# Schematic.net
KiCad netlist of a schematic drawn in Altium Designer
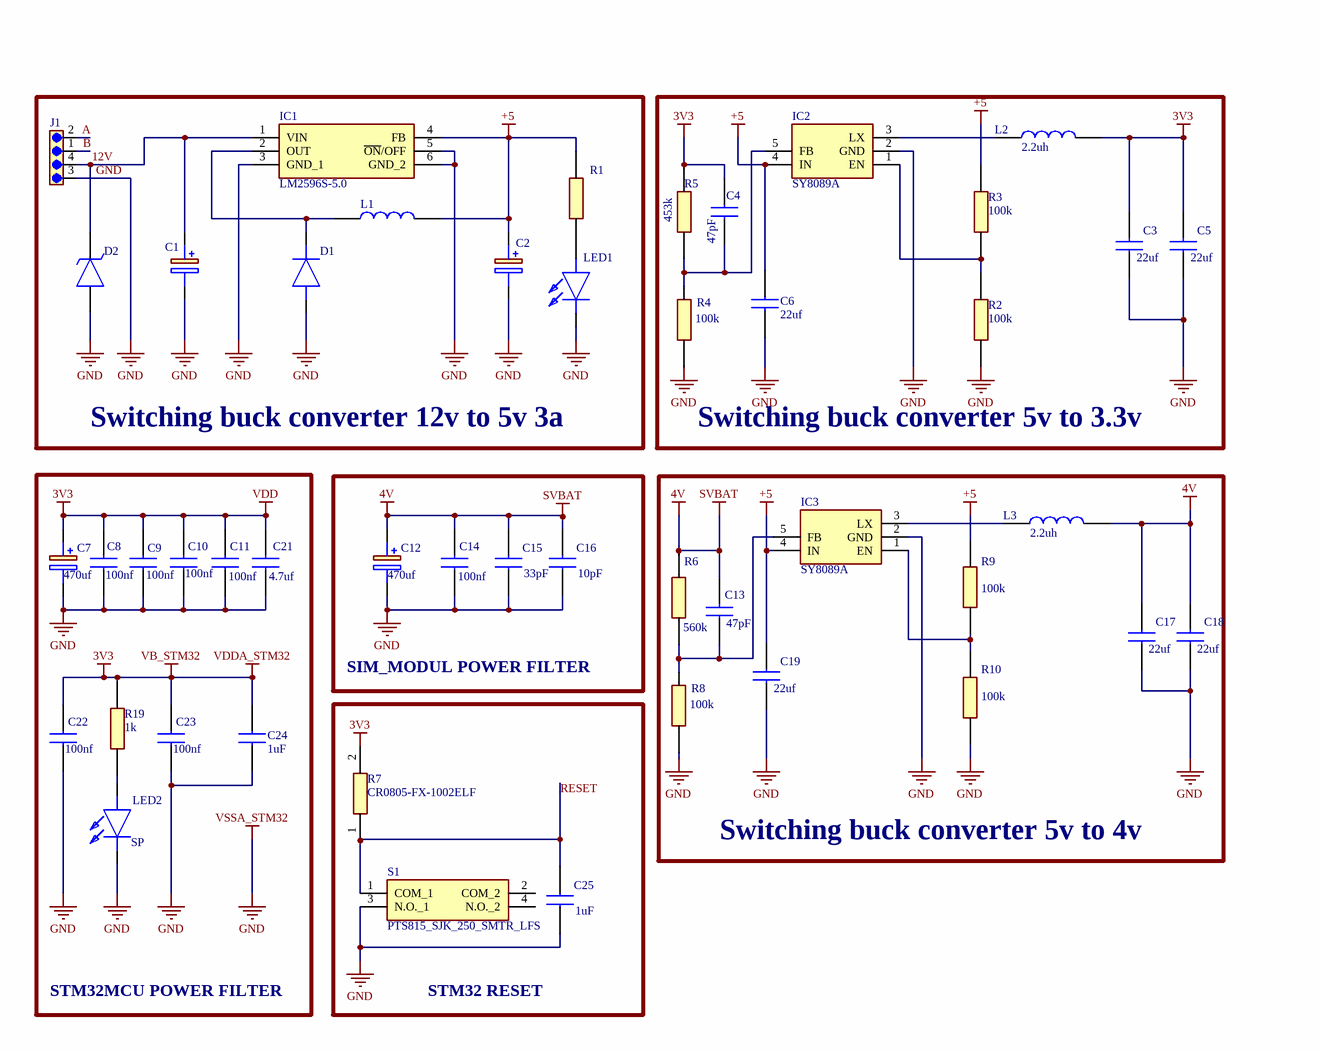
[diagram p0: Schematic.SchDoc, left]

(export (version "E")
  (design (tool "Eeschema 10.0.6"))
  (components
    (comp (ref "C1")
      (value "B40900B5477M000")
      (footprint "BGA129C50P13X13_700X700X60:CAPAE1030X1280N")
      (description "Capacitor Polarised")
      (fields (field (name "MOUSER PART NUMBER") "871-B40900B5477M000"))
      (libsource (lib "*") (part "B40900B5477M000"))
    )
    (comp (ref "C2")
      (value "220uf")
      (footprint "BGA129C50P13X13_700X700X60:CAPPM7344X310N")
      (description "Capacitor Polarised 220uf 10v smd tantalum Part Number: TAJD227K010RNJ")
      (fields
        (field (name "MANUFACTURER_PART_NUMBER") "TAJD227K010RNJ")
        (field (name "MOUSER PART NUMBER") "581-TAJD227K010R")
      )
      (libsource (lib "*") (part "TAJD227K010RNJ"))
    )
    (comp (ref "C3")
      (value "22uf")
      (footprint "BGA129C50P13X13_700X700X60:CAPC2012X140N")
      (description "Capacitor")
      (fields (field (name "MANUFACTURER_PART_NUMBER") "CL21X226MQQNNNE"))
      (libsource (lib "*") (part "CL21X226MQQNNNE"))
    )
    (comp (ref "C4")
      (value "47pF")
      (footprint "BGA129C50P13X13_700X700X60:C0603")
      (description "Capacitor Part Number: C0603H470J5GACTU 47pf 50v 0603")
      (fields
        (field (name "MANUFACTURER_PART_NUMBER") "C0603H470J5GACTU")
        (field (name "MOUSER PART NUMBER") "80-C0603H470J5GACTU")
      )
      (libsource (lib "STM32WB55VGQ6") (part "C0603H470J5GACTU"))
    )
    (comp (ref "C5")
      (value "22uf")
      (footprint "BGA129C50P13X13_700X700X60:CAPC2012X140N")
      (description "Capacitor")
      (fields (field (name "MANUFACTURER_PART_NUMBER") "CL21X226MQQNNNE"))
      (libsource (lib "*") (part "CL21X226MQQNNNE"))
    )
    (comp (ref "C6")
      (value "22uf")
      (footprint "BGA129C50P13X13_700X700X60:CAPC2012X140N")
      (description "Capacitor")
      (fields (field (name "MANUFACTURER_PART_NUMBER") "CL21X226MQQNNNE"))
      (libsource (lib "*") (part "CL21X226MQQNNNE"))
    )
    (comp (ref "C7")
      (value "470uf")
      (footprint "BGA129C50P13X13_700X700X60:T495D")
      (description "Capacitor Polarised")
      (fields
        (field (name "MANUFACTURER_PART_NUMBER") "T495D477K006ATE100")
        (field (name "MOUSER PART NUMBER") "80-T495D477K006E100")
      )
      (libsource (lib "STM32WB55VGQ6") (part "T495D477K006ATE100"))
    )
    (comp (ref "C8")
      (value "100nf")
      (footprint "BGA129C50P13X13_700X700X60:CAPC1608X90N")
      (description "Capacitor")
      (fields
        (field (name "MANUFACTURER_PART_NUMBER") "06036C104MAZ2A")
        (field (name "MOUSER PART NUMBER") "581-06036C104MAZ2A")
      )
      (libsource (lib "*") (part "06036C104MAZ2A"))
    )
    (comp (ref "C9")
      (value "100nf")
      (footprint "BGA129C50P13X13_700X700X60:CAPC1608X90N")
      (description "Capacitor")
      (fields
        (field (name "MANUFACTURER_PART_NUMBER") "06036C104MAZ2A")
        (field (name "MOUSER PART NUMBER") "581-06036C104MAZ2A")
      )
      (libsource (lib "*") (part "06036C104MAZ2A"))
    )
    (comp (ref "C10")
      (value "100nf")
      (footprint "BGA129C50P13X13_700X700X60:CAPC1608X90N")
      (description "Capacitor")
      (fields
        (field (name "MANUFACTURER_PART_NUMBER") "06036C104MAZ2A")
        (field (name "MOUSER PART NUMBER") "581-06036C104MAZ2A")
      )
      (libsource (lib "*") (part "06036C104MAZ2A"))
    )
    (comp (ref "C11")
      (value "100nf")
      (footprint "BGA129C50P13X13_700X700X60:CAPC1608X90N")
      (description "Capacitor")
      (fields
        (field (name "MANUFACTURER_PART_NUMBER") "06036C104MAZ2A")
        (field (name "MOUSER PART NUMBER") "581-06036C104MAZ2A")
      )
      (libsource (lib "*") (part "06036C104MAZ2A"))
    )
    (comp (ref "C12")
      (value "470uf")
      (footprint "BGA129C50P13X13_700X700X60:T495D")
      (description "Capacitor Polarised")
      (fields
        (field (name "MANUFACTURER_PART_NUMBER") "T495D477K006ATE100")
        (field (name "MOUSER PART NUMBER") "80-T495D477K006E100")
      )
      (libsource (lib "STM32WB55VGQ6") (part "T495D477K006ATE100"))
    )
    (comp (ref "C13")
      (value "47pF")
      (footprint "BGA129C50P13X13_700X700X60:C0603")
      (description "Capacitor Part Number: C0603H470J5GACTU 47pf 50v 0603")
      (fields
        (field (name "MANUFACTURER_PART_NUMBER") "C0603H470J5GACTU")
        (field (name "MOUSER PART NUMBER") "80-C0603H470J5GACTU")
      )
      (libsource (lib "STM32WB55VGQ6") (part "C0603H470J5GACTU"))
    )
    (comp (ref "C14")
      (value "100nf")
      (footprint "BGA129C50P13X13_700X700X60:CAPC1608X90N")
      (description "Capacitor")
      (fields
        (field (name "MANUFACTURER_PART_NUMBER") "06036C104MAZ2A")
        (field (name "MOUSER PART NUMBER") "581-06036C104MAZ2A")
      )
      (libsource (lib "*") (part "06036C104MAZ2A"))
    )
    (comp (ref "C15")
      (value "33pF")
      (footprint "BGA129C50P13X13_700X700X60:CAPC0603X33N")
      (description "Capacitor")
      (fields
        (field (name "MANUFACTURER_PART_NUMBER") "GJM0335C0J330JB01D")
        (field (name "MOUSER PART NUMBER") "81-GJM0335C0J330JB1D")
      )
      (libsource (lib "*") (part "GJM0335C0J330JB01D"))
    )
    (comp (ref "C16")
      (value "10pF")
      (footprint "BGA129C50P13X13_700X700X60:CAPC1608X90N")
      (description "Capacitor")
      (fields
        (field (name "MANUFACTURER_PART_NUMBER") "CC0603JRNPO9BN100")
        (field (name "MOUSER PART NUMBER") "603-C0603JRNPO9BN100")
      )
      (libsource (lib "*") (part "CC0603JRNPO9BN100"))
    )
    (comp (ref "C17")
      (value "22uf")
      (footprint "BGA129C50P13X13_700X700X60:CAPC2012X140N")
      (description "Capacitor")
      (fields (field (name "MANUFACTURER_PART_NUMBER") "CL21X226MQQNNNE"))
      (libsource (lib "*") (part "CL21X226MQQNNNE"))
    )
    (comp (ref "C18")
      (value "22uf")
      (footprint "BGA129C50P13X13_700X700X60:CAPC2012X140N")
      (description "Capacitor")
      (fields (field (name "MANUFACTURER_PART_NUMBER") "CL21X226MQQNNNE"))
      (libsource (lib "*") (part "CL21X226MQQNNNE"))
    )
    (comp (ref "C19")
      (value "22uf")
      (footprint "BGA129C50P13X13_700X700X60:CAPC2012X140N")
      (description "Capacitor")
      (fields (field (name "MANUFACTURER_PART_NUMBER") "CL21X226MQQNNNE"))
      (libsource (lib "*") (part "CL21X226MQQNNNE"))
    )
    (comp (ref "C21")
      (value "4.7uf")
      (footprint "BGA129C50P13X13_700X700X60:CAPC2012X152N")
      (description "Capacitor")
      (fields
        (field (name "MANUFACTURER_PART_NUMBER") "08056D475MAT2A")
        (field (name "MOUSER PART NUMBER") "581-08056D475M")
      )
      (libsource (lib "*") (part "08056D475MAT2A"))
    )
    (comp (ref "C22")
      (value "100nf")
      (footprint "BGA129C50P13X13_700X700X60:CAPC1608X90N")
      (description "Capacitor")
      (fields
        (field (name "MANUFACTURER_PART_NUMBER") "06036C104MAZ2A")
        (field (name "MOUSER PART NUMBER") "581-06036C104MAZ2A")
      )
      (libsource (lib "*") (part "06036C104MAZ2A"))
    )
    (comp (ref "C23")
      (value "100nf")
      (footprint "BGA129C50P13X13_700X700X60:CAPC1608X90N")
      (description "Capacitor")
      (fields
        (field (name "MANUFACTURER_PART_NUMBER") "06036C104MAZ2A")
        (field (name "MOUSER PART NUMBER") "581-06036C104MAZ2A")
      )
      (libsource (lib "*") (part "06036C104MAZ2A"))
    )
    (comp (ref "C24")
      (value "1uF")
      (footprint "BGA129C50P13X13_700X700X60:CAPC1608X90N")
      (description "Capacitor")
      (fields
        (field (name "MANUFACTURER_PART_NUMBER") "06036C105MAT2A")
        (field (name "MOUSER PART NUMBER") "581-06036C105MAT2A")
      )
      (libsource (lib "STM32WB55VGQ6") (part "06036C105MAT2A"))
    )
    (comp (ref "C25")
      (value "1uF")
      (footprint "BGA129C50P13X13_700X700X60:CAPC1608X90N")
      (description "Capacitor")
      (fields
        (field (name "MANUFACTURER_PART_NUMBER") "06036C105MAT2A")
        (field (name "MOUSER PART NUMBER") "581-06036C105MAT2A")
      )
      (libsource (lib "STM32WB55VGQ6") (part "06036C105MAT2A"))
    )
    (comp (ref "D1")
      (value "SS54B")
      (footprint "BGA129C50P13X13_700X700X60:DIOM5336X244N")
      (description "Diode")
      (libsource (lib "*") (part "SS54B"))
    )
    (comp (ref "D2")
      (value "ESDA17P50-1U1M")
      (footprint "BGA129C50P13X13_700X700X60:ESDA17P501U1M")
      (description "TVS Diode (Uni-directional)")
      (fields (field (name "MOUSER PART NUMBER") "511-ESDA17P50-1U1M"))
      (libsource (lib "*") (part "ESDA17P50-1U1M"))
    )
    (comp (ref "IC1")
      (value "LM2596S-5.0")
      (footprint "BGA129C50P13X13_700X700X60:KTT0005B")
      (description "Integrated Circuit")
      (fields (field (name "MOUSER PART NUMBER") "926-LM2596S-50"))
      (libsource (lib "*") (part "LM2596S-5.0"))
    )
    (comp (ref "IC2")
      (value "SY8089A")
      (footprint "BGA129C50P13X13_700X700X60:SOT95P285X140-5N")
      (description "Integrated Circuit")
      (libsource (lib "*") (part "SY8089A"))
    )
    (comp (ref "IC3")
      (value "SY8089A")
      (footprint "BGA129C50P13X13_700X700X60:SOT95P285X140-5N")
      (description "Integrated Circuit")
      (libsource (lib "*") (part "SY8089A"))
    )
    (comp (ref "J1")
      (value "691322310004")
      (footprint "691322310004")
      (fields (field (name "MF") "Wurth Electronics"))
      (libsource (lib "691322310004") (part "691322310004"))
    )
    (comp (ref "L1")
      (value "SRR1260-330M")
      (footprint "BGA129C50P13X13_700X700X60:SRR1260-150M")
      (description "Inductor 33uH")
      (fields (field (name "MOUSER PART NUMBER") "652-SRR1260-330M"))
      (libsource (lib "*") (part "SRR1260-330M"))
    )
    (comp (ref "L2")
      (value "2.2uh")
      (footprint "BGA129C50P13X13_700X700X60:MPLAL50302R2")
      (description "Inductor Part Number :MPL-AL5030-2R2")
      (fields
        (field (name "MANUFACTURER_PART_NUMBER") "MPL-AL5030-2R2")
        (field (name "MOUSER PART NUMBER") "946-MPL-AL5030-2R2")
      )
      (libsource (lib "*") (part "MPL-AL5030-2R2"))
    )
    (comp (ref "L3")
      (value "2.2uh")
      (footprint "BGA129C50P13X13_700X700X60:MPLAL50302R2")
      (description "Inductor Part Number :MPL-AL5030-2R2")
      (fields
        (field (name "MANUFACTURER_PART_NUMBER") "MPL-AL5030-2R2")
        (field (name "MOUSER PART NUMBER") "946-MPL-AL5030-2R2")
      )
      (libsource (lib "*") (part "MPL-AL5030-2R2"))
    )
    (comp (ref "LED1")
      (value "150080GS75000")
      (footprint "BGA129C50P13X13_700X700X60:LEDM2012X80N")
      (description "LED")
      (fields (field (name "MOUSER PART NUMBER") "710-150080GS75000"))
      (libsource (lib "*") (part "150080GS75000"))
    )
    (comp (ref "LED2")
      (value "SP")
      (footprint "BGA129C50P13X13_700X700X60:LEDC2012X110N")
      (description "LED")
      (fields
        (field (name "MANUFACTURER_PART_NUMBER") "SM0805RC")
        (field (name "MOUSER PART NUMBER") "749-SM0805RC")
      )
      (libsource (lib "*") (part "SM0805RC"))
    )
    (comp (ref "R1")
      (value "150R")
      (footprint "BGA129C50P13X13_700X700X60:RESC2012X65N")
      (description "Resistor 0805 150R 1/4W")
      (fields
        (field (name "MANUFACTURER_PART_NUMBER") "RMCF0805FT150R")
        (field (name "MOUSER PART NUMBER") "708-RMCF0805FT150R")
      )
      (libsource (lib "*") (part "RMCF0805FT150R"))
    )
    (comp (ref "R2")
      (value "100k")
      (footprint "BGA129C50P13X13_700X700X60:RESC2012X60N")
      (description "Resistor")
      (fields
        (field (name "MANUFACTURER_PART_NUMBER") "CR0805-FX-1003ELF")
        (field (name "MOUSER PART NUMBER") "652-CR0805FX-1003ELF")
      )
      (libsource (lib "*") (part "CR0805-FX-1003ELF"))
    )
    (comp (ref "R3")
      (value "100k")
      (footprint "BGA129C50P13X13_700X700X60:RESC2012X60N")
      (description "Resistor")
      (fields
        (field (name "MANUFACTURER_PART_NUMBER") "CR0805-FX-1003ELF")
        (field (name "MOUSER PART NUMBER") "652-CR0805FX-1003ELF")
      )
      (libsource (lib "*") (part "CR0805-FX-1003ELF"))
    )
    (comp (ref "R4")
      (value "100k")
      (footprint "BGA129C50P13X13_700X700X60:RESC2012X60N")
      (description "Resistor")
      (fields
        (field (name "MANUFACTURER_PART_NUMBER") "CR0805-FX-1003ELF")
        (field (name "MOUSER PART NUMBER") "652-CR0805FX-1003ELF")
      )
      (libsource (lib "*") (part "CR0805-FX-1003ELF"))
    )
    (comp (ref "R5")
      (value "453k")
      (footprint "BGA129C50P13X13_700X700X60:RESC2012X60N")
      (description "Resistor 453k 0805 1/4w")
      (fields
        (field (name "MANUFACTURER_PART_NUMBER") "RK73H2ATTD4533F")
        (field (name "MOUSER PART NUMBER") "660-RK73H2ATTD4533F")
      )
      (libsource (lib "*") (part "RK73H2ATTD4533F"))
    )
    (comp (ref "R6")
      (value "560k")
      (footprint "BGA129C50P13X13_700X700X60:RESC2012X65N")
      (description "Resistor")
      (fields (field (name "MANUFACTURER_PART_NUMBER") "CPF0805B560KE"))
      (libsource (lib "*") (part "CPF0805B560KE"))
    )
    (comp (ref "R7")
      (value "CR0805-FX-1002ELF")
      (footprint "BGA129C50P13X13_700X700X60:RESC2012X60N")
      (description "Resistor")
      (fields (field (name "MOUSER PART NUMBER") "652-CR0805FX-1002ELF"))
      (libsource (lib "STM32WB55VGQ6") (part "CR0805-FX-1002ELF"))
    )
    (comp (ref "R8")
      (value "100k")
      (footprint "BGA129C50P13X13_700X700X60:RESC2012X60N")
      (description "Resistor")
      (fields
        (field (name "MANUFACTURER_PART_NUMBER") "CR0805-FX-1003ELF")
        (field (name "MOUSER PART NUMBER") "652-CR0805FX-1003ELF")
      )
      (libsource (lib "*") (part "CR0805-FX-1003ELF"))
    )
    (comp (ref "R9")
      (value "100k")
      (footprint "BGA129C50P13X13_700X700X60:RESC2012X60N")
      (description "Resistor")
      (fields
        (field (name "MANUFACTURER_PART_NUMBER") "CR0805-FX-1003ELF")
        (field (name "MOUSER PART NUMBER") "652-CR0805FX-1003ELF")
      )
      (libsource (lib "*") (part "CR0805-FX-1003ELF"))
    )
    (comp (ref "R10")
      (value "100k")
      (footprint "BGA129C50P13X13_700X700X60:RESC2012X60N")
      (description "Resistor")
      (fields
        (field (name "MANUFACTURER_PART_NUMBER") "CR0805-FX-1003ELF")
        (field (name "MOUSER PART NUMBER") "652-CR0805FX-1003ELF")
      )
      (libsource (lib "*") (part "CR0805-FX-1003ELF"))
    )
    (comp (ref "R19")
      (value "1k")
      (footprint "BGA129C50P13X13_700X700X60:RESC1005X40N")
      (description "Resistor")
      (fields
        (field (name "MANUFACTURER_PART_NUMBER") "RC0402JR-071KL")
        (field (name "MOUSER PART NUMBER") "603-RC0402JR-071KL")
      )
      (libsource (lib "*") (part "RC0402JR-071KL"))
    )
    (comp (ref "S1")
      (value "PTS815_SJK_250_SMTR_LFS")
      (footprint "BGA129C50P13X13_700X700X60:PTS815SJK250SMTRLFS")
      (description "Switch")
      (fields
        (field (name "MANUFACTURER_PART_NUMBER") "PTS815 SJK 250 SMTR LFS")
        (field (name "MOUSER PART NUMBER") "611-PTS815SJK250SMTR")
      )
      (libsource (lib "*") (part "PTS815_SJK_250_SMTR_LFS"))
    )
  )
  (nets
    (net (code "1") (name "+5") (class "Default")
      (node (ref "C19") (pin "2") (pinfunction "2_2") (pintype "passive"))
      (node (ref "C2") (pin "1") (pinfunction "+_1") (pintype "passive"))
      (node (ref "C6") (pin "2") (pinfunction "2_2") (pintype "passive"))
      (node (ref "IC1") (pin "4") (pinfunction "FB_4") (pintype "passive"))
      (node (ref "IC2") (pin "4") (pinfunction "IN_4") (pintype "passive"))
      (node (ref "IC3") (pin "4") (pinfunction "IN_4") (pintype "passive"))
      (node (ref "L1") (pin "2") (pinfunction "2_2") (pintype "passive"))
      (node (ref "R1") (pin "2") (pinfunction "2_2") (pintype "passive"))
      (node (ref "R3") (pin "2") (pinfunction "2_2") (pintype "passive"))
      (node (ref "R9") (pin "2") (pinfunction "2_2") (pintype "passive"))
    )
    (net (code "2") (name "/12V") (class "Default")
      (node (ref "C1") (pin "1") (pinfunction "+_1") (pintype "passive"))
      (node (ref "D2") (pin "1") (pinfunction "K_1") (pintype "passive"))
      (node (ref "IC1") (pin "1") (pinfunction "VIN_1") (pintype "passive"))
      (node (ref "J1") (pin "4") (pinfunction "4_4") (pintype "passive"))
    )
    (net (code "3") (name "/A") (class "Default")
      (node (ref "J1") (pin "2") (pinfunction "2_2") (pintype "passive"))
    )
    (net (code "4") (name "/B") (class "Default")
      (node (ref "J1") (pin "1") (pinfunction "1_1") (pintype "passive"))
    )
    (net (code "5") (name "/RESET") (class "Default")
      (node (ref "C25") (pin "2") (pinfunction "2_2") (pintype "passive"))
      (node (ref "R7") (pin "1") (pinfunction "1_1") (pintype "passive"))
      (node (ref "S1") (pin "1") (pinfunction "COM_1_1") (pintype "passive"))
    )
    (net (code "6") (name "3V3") (class "Default")
      (node (ref "C10") (pin "2") (pinfunction "2_2") (pintype "passive"))
      (node (ref "C11") (pin "2") (pinfunction "2_2") (pintype "passive"))
      (node (ref "C21") (pin "2") (pinfunction "2_2") (pintype "passive"))
      (node (ref "C22") (pin "2") (pinfunction "2_2") (pintype "passive"))
      (node (ref "C23") (pin "2") (pinfunction "2_2") (pintype "passive"))
      (node (ref "C24") (pin "2") (pinfunction "2_2") (pintype "passive"))
      (node (ref "C3") (pin "2") (pinfunction "2_2") (pintype "passive"))
      (node (ref "C4") (pin "2") (pinfunction "2_2") (pintype "passive"))
      (node (ref "C5") (pin "2") (pinfunction "2_2") (pintype "passive"))
      (node (ref "C7") (pin "1") (pinfunction "+_1") (pintype "passive"))
      (node (ref "C8") (pin "2") (pinfunction "2_2") (pintype "passive"))
      (node (ref "C9") (pin "2") (pinfunction "2_2") (pintype "passive"))
      (node (ref "L2") (pin "2") (pinfunction "2_2") (pintype "passive"))
      (node (ref "R19") (pin "2") (pinfunction "2_2") (pintype "passive"))
      (node (ref "R5") (pin "2") (pinfunction "2_2") (pintype "passive"))
      (node (ref "R7") (pin "2") (pinfunction "2_2") (pintype "passive"))
    )
    (net (code "7") (name "4V") (class "Default")
      (node (ref "C12") (pin "1") (pinfunction "+_1") (pintype "passive"))
      (node (ref "C13") (pin "2") (pinfunction "2_2") (pintype "passive"))
      (node (ref "C14") (pin "2") (pinfunction "2_2") (pintype "passive"))
      (node (ref "C15") (pin "2") (pinfunction "2_2") (pintype "passive"))
      (node (ref "C16") (pin "2") (pinfunction "C2_2") (pintype "passive"))
      (node (ref "C17") (pin "2") (pinfunction "2_2") (pintype "passive"))
      (node (ref "C18") (pin "2") (pinfunction "2_2") (pintype "passive"))
      (node (ref "L3") (pin "2") (pinfunction "2_2") (pintype "passive"))
      (node (ref "R6") (pin "2") (pinfunction "2_2") (pintype "passive"))
    )
    (net (code "8") (name "GND") (class "Default")
      (node (ref "C1") (pin "2") (pinfunction "-_2") (pintype "passive"))
      (node (ref "C10") (pin "1") (pinfunction "1_1") (pintype "passive"))
      (node (ref "C11") (pin "1") (pinfunction "1_1") (pintype "passive"))
      (node (ref "C12") (pin "2") (pinfunction "-_2") (pintype "passive"))
      (node (ref "C14") (pin "1") (pinfunction "1_1") (pintype "passive"))
      (node (ref "C15") (pin "1") (pinfunction "1_1") (pintype "passive"))
      (node (ref "C16") (pin "1") (pinfunction "C1_1") (pintype "passive"))
      (node (ref "C17") (pin "1") (pinfunction "1_1") (pintype "passive"))
      (node (ref "C18") (pin "1") (pinfunction "1_1") (pintype "passive"))
      (node (ref "C19") (pin "1") (pinfunction "1_1") (pintype "passive"))
      (node (ref "C2") (pin "2") (pinfunction "-_2") (pintype "passive"))
      (node (ref "C21") (pin "1") (pinfunction "1_1") (pintype "passive"))
      (node (ref "C22") (pin "1") (pinfunction "1_1") (pintype "passive"))
      (node (ref "C23") (pin "1") (pinfunction "1_1") (pintype "passive"))
      (node (ref "C24") (pin "1") (pinfunction "1_1") (pintype "passive"))
      (node (ref "C25") (pin "1") (pinfunction "1_1") (pintype "passive"))
      (node (ref "C3") (pin "1") (pinfunction "1_1") (pintype "passive"))
      (node (ref "C5") (pin "1") (pinfunction "1_1") (pintype "passive"))
      (node (ref "C6") (pin "1") (pinfunction "1_1") (pintype "passive"))
      (node (ref "C7") (pin "2") (pinfunction "-_2") (pintype "passive"))
      (node (ref "C8") (pin "1") (pinfunction "1_1") (pintype "passive"))
      (node (ref "C9") (pin "1") (pinfunction "1_1") (pintype "passive"))
      (node (ref "D1") (pin "2") (pinfunction "A_2") (pintype "passive"))
      (node (ref "D2") (pin "2") (pinfunction "A_2") (pintype "passive"))
      (node (ref "IC1") (pin "3") (pinfunction "GND_1_3") (pintype "passive"))
      (node (ref "IC1") (pin "5") (pinfunction "~{ON}/OFF_5") (pintype "passive"))
      (node (ref "IC1") (pin "6") (pinfunction "GND_2_6") (pintype "passive"))
      (node (ref "IC2") (pin "2") (pinfunction "GND_2") (pintype "passive"))
      (node (ref "IC3") (pin "2") (pinfunction "GND_2") (pintype "passive"))
      (node (ref "J1") (pin "3") (pinfunction "3_3") (pintype "passive"))
      (node (ref "LED1") (pin "1") (pinfunction "K_1") (pintype "passive"))
      (node (ref "LED2") (pin "1") (pinfunction "K_1") (pintype "passive"))
      (node (ref "R10") (pin "1") (pinfunction "1_1") (pintype "passive"))
      (node (ref "R2") (pin "1") (pinfunction "1_1") (pintype "passive"))
      (node (ref "R4") (pin "1") (pinfunction "1_1") (pintype "passive"))
      (node (ref "R8") (pin "1") (pinfunction "1_1") (pintype "passive"))
      (node (ref "S1") (pin "3") (pinfunction "N.O._1_3") (pintype "passive"))
    )
    (net (code "9") (name "Net-(D1-K)") (class "Default")
      (node (ref "D1") (pin "1") (pinfunction "K_1") (pintype "passive"))
      (node (ref "IC1") (pin "2") (pinfunction "OUT_2") (pintype "passive"))
      (node (ref "L1") (pin "1") (pinfunction "1_1") (pintype "passive"))
    )
    (net (code "10") (name "Net-(IC2-EN)") (class "Default")
      (node (ref "IC2") (pin "1") (pinfunction "EN_1") (pintype "passive"))
      (node (ref "R2") (pin "2") (pinfunction "2_2") (pintype "passive"))
      (node (ref "R3") (pin "1") (pinfunction "1_1") (pintype "passive"))
    )
    (net (code "11") (name "Net-(IC2-FB)") (class "Default")
      (node (ref "C4") (pin "1") (pinfunction "1_1") (pintype "passive"))
      (node (ref "IC2") (pin "5") (pinfunction "FB_5") (pintype "passive"))
      (node (ref "R4") (pin "2") (pinfunction "2_2") (pintype "passive"))
      (node (ref "R5") (pin "1") (pinfunction "1_1") (pintype "passive"))
    )
    (net (code "12") (name "Net-(IC2-LX)") (class "Default")
      (node (ref "IC2") (pin "3") (pinfunction "LX_3") (pintype "passive"))
      (node (ref "L2") (pin "1") (pinfunction "1_1") (pintype "passive"))
    )
    (net (code "13") (name "Net-(IC3-EN)") (class "Default")
      (node (ref "IC3") (pin "1") (pinfunction "EN_1") (pintype "passive"))
      (node (ref "R10") (pin "2") (pinfunction "2_2") (pintype "passive"))
      (node (ref "R9") (pin "1") (pinfunction "1_1") (pintype "passive"))
    )
    (net (code "14") (name "Net-(IC3-FB)") (class "Default")
      (node (ref "C13") (pin "1") (pinfunction "1_1") (pintype "passive"))
      (node (ref "IC3") (pin "5") (pinfunction "FB_5") (pintype "passive"))
      (node (ref "R6") (pin "1") (pinfunction "1_1") (pintype "passive"))
      (node (ref "R8") (pin "2") (pinfunction "2_2") (pintype "passive"))
    )
    (net (code "15") (name "Net-(IC3-LX)") (class "Default")
      (node (ref "IC3") (pin "3") (pinfunction "LX_3") (pintype "passive"))
      (node (ref "L3") (pin "1") (pinfunction "1_1") (pintype "passive"))
    )
    (net (code "16") (name "Net-(LED1-A)") (class "Default")
      (node (ref "LED1") (pin "2") (pinfunction "A_2") (pintype "passive"))
      (node (ref "R1") (pin "1") (pinfunction "1_1") (pintype "passive"))
    )
    (net (code "17") (name "Net-(LED2-A)") (class "Default")
      (node (ref "LED2") (pin "2") (pinfunction "A_2") (pintype "passive"))
      (node (ref "R19") (pin "1") (pinfunction "1_1") (pintype "passive"))
    )
    (net (code "18") (name "unconnected-(S1-COM_2-Pad2)") (class "Default")
      (node (ref "S1") (pin "2") (pinfunction "COM_2_2") (pintype "passive"))
    )
    (net (code "19") (name "unconnected-(S1-N.O._2-Pad4)") (class "Default")
      (node (ref "S1") (pin "4") (pinfunction "N.O._2_4") (pintype "passive"))
    )
  )
)
